# Z_line_07.net
KiCad netlist of a schematic drawn in Altium Designer
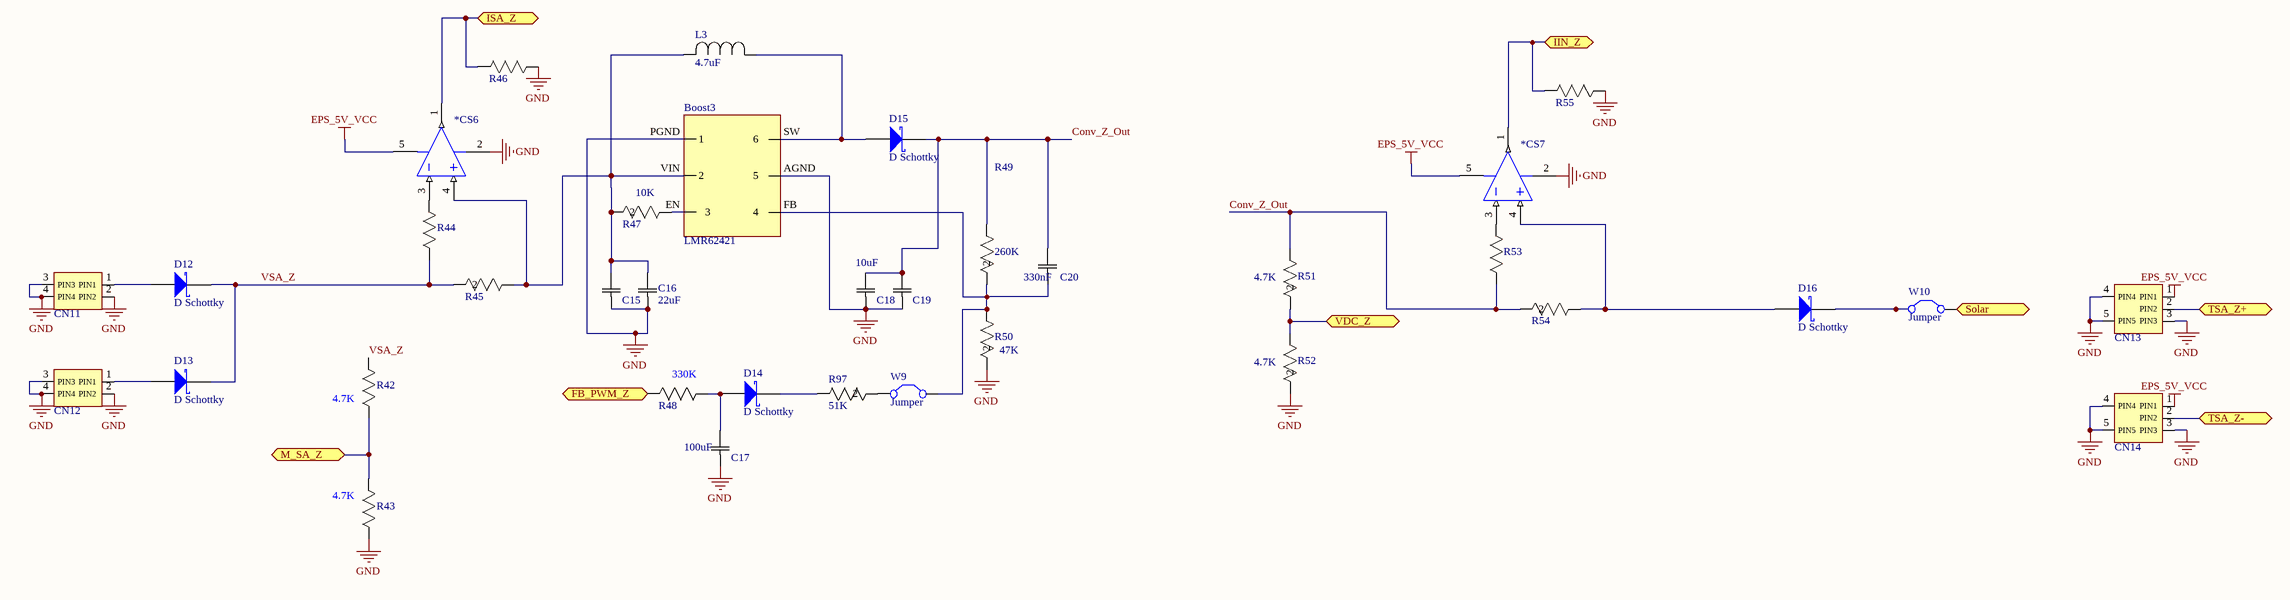
[diagram p0: Z_line_07.SchDoc]

(export (version "E")
  (design (tool "Eeschema 10.0.6"))
  (components
    (comp (ref "*CS6")
      (value "CS6")
      (footprint "LT-S5-5-TSOT-23_N")
      (fields
        (field (name "LINEAR TECHNOLOGY PART NUMBER") "LT6106")
        (field (name "MANUFACTURER") "Linear Technology")
        (field (name "PARTNUMBER") "LT6106HS5#TRMPBF")
      )
      (libsource (lib "Linear Technology Operational Amplifiers (LT2000-LT6000)") (part "LT6106HS5#TRMPBF"))
    )
    (comp (ref "*CS7")
      (value "CS7")
      (footprint "LT-S5-5-TSOT-23_N")
      (fields
        (field (name "LINEAR TECHNOLOGY PART NUMBER") "LT6106")
        (field (name "MANUFACTURER") "Linear Technology")
        (field (name "PARTNUMBER") "LT6106HS5#TRMPBF")
      )
      (libsource (lib "Linear Technology Operational Amplifiers (LT2000-LT6000)") (part "LT6106HS5#TRMPBF"))
    )
    (comp (ref "Boost3")
      (value "LMR62421")
      (footprint "PcbLib_2:LMR62421")
      (description "LMR62421XSDDEMO: 12V @ 500mA, 2.7 ~ 5.5V in")
      (libsource (lib "LMR62421_2") (part "Component_1"))
    )
    (comp (ref "C15")
      (value "GRM155R71H103KA8")
      (footprint "RC0805N")
      (description "Ceramic Capacitor 0402")
      (fields
        (field (name "MANUFACTURER_PART_NUMBER") "GRM155R71H103KA88D")
        (field (name "COPYRIGHT") "Copyright (C) 2015 Accelerated Designs. All rights reserved")
      )
      (libsource (lib "Schlib1") (part "GRM155R71H103KA8"))
    )
    (comp (ref "C16")
      (value "22uF")
      (footprint "RC0805N")
      (description "Ceramic Capacitor")
      (fields
        (field (name "MANUFACTURER_PART_NUMBER") "GRM155R71H103KA88D")
        (field (name "COPYRIGHT") "Copyright (C) 2015 Accelerated Designs. All rights reserved")
      )
      (libsource (lib "PCDU_Library") (part "GRM155R71H103KA8"))
    )
    (comp (ref "C17")
      (value "100uF")
      (footprint "RC0805N")
      (description "Ceramic Capacitor 47uF 0603")
      (fields
        (field (name "MANUFACTURER_PART_NUMBER") "GRM188R71H472KA01D")
        (field (name "COPYRIGHT") "Copyright (C) 2015 Accelerated Designs. All rights reserved")
      )
      (libsource (lib "Schlib1") (part "GRM188R71H472KA0"))
    )
    (comp (ref "C18")
      (value "10uF")
      (footprint "PcbLib1:RC0805N")
      (description "Ceramic Capacitor 47uF 0603")
      (fields
        (field (name "MANUFACTURER_PART_NUMBER") "GRM188R71H472KA01D")
        (field (name "COPYRIGHT") "Copyright (C) 2015 Accelerated Designs. All rights reserved")
      )
      (libsource (lib "PCDU_Library") (part "GRM188R71H472KA0"))
    )
    (comp (ref "C19")
      (value "GRM155R71H103KA8")
      (footprint "RC0805N")
      (description "Ceramic Capacitor 0402")
      (fields
        (field (name "MANUFACTURER_PART_NUMBER") "GRM155R71H103KA88D")
        (field (name "COPYRIGHT") "Copyright (C) 2015 Accelerated Designs. All rights reserved")
      )
      (libsource (lib "Schlib1") (part "GRM155R71H103KA8"))
    )
    (comp (ref "C20")
      (value "330nF")
      (footprint "RC0805N")
      (description "Ceramic Capacitor")
      (fields
        (field (name "MANUFACTURER_PART_NUMBER") "GRM155R71H103KA88D")
        (field (name "COPYRIGHT") "Copyright (C) 2015 Accelerated Designs. All rights reserved")
      )
      (libsource (lib "PCDU_Library") (part "GRM155R71H103KA8"))
    )
    (comp (ref "CN11")
      (value "SM02B-SRSS")
      (footprint "2pins")
      (description "CONN HEADER SH 2POS SIDE 1MM TIN")
      (fields
        (field (name "DIGI-KEY PART NUMBER") "455-1802-1-ND")
        (field (name "MANUFACTURER PART NUMBER") "SM02B-SRSS-TB(LF)(SN)")
      )
      (libsource (lib "EPS_lib") (part "2Pin_Connector"))
    )
    (comp (ref "CN12")
      (value "SM02B-SRSS")
      (footprint "2pins")
      (description "CONN HEADER SH 2POS SIDE 1MM TIN")
      (fields
        (field (name "DIGI-KEY PART NUMBER") "455-1802-1-ND")
        (field (name "MANUFACTURER PART NUMBER") "SM02B-SRSS-TB(LF)(SN)")
      )
      (libsource (lib "EPS_lib") (part "2Pin_Connector"))
    )
    (comp (ref "CN13")
      (value "SM03B-SRSS")
      (footprint "PcbLib1:3pins")
      (description "CONN HEADER SH 3POS SIDE 1MM TIN")
      (fields
        (field (name "DIGI-KEY PART NUMBER") "455-1803-1-ND")
        (field (name "MANUFACTURER PART NUMBER") "SM03B-SRSS-TB(LF)(SN)")
      )
      (libsource (lib "EPS_lib") (part "3PIN_Connector"))
    )
    (comp (ref "CN14")
      (value "SM03B-SRSS")
      (footprint "PcbLib1:3pins")
      (description "CONN HEADER SH 3POS SIDE 1MM TIN")
      (fields
        (field (name "DIGI-KEY PART NUMBER") "455-1803-1-ND")
        (field (name "MANUFACTURER PART NUMBER") "SM03B-SRSS-TB(LF)(SN)")
      )
      (libsource (lib "EPS_lib") (part "3PIN_Connector"))
    )
    (comp (ref "D12")
      (value "D Schottky")
      (footprint "SMB")
      (description "Schottky Diode, 1A")
      (fields (field (name "PUBLISHER") "Altium Limited"))
      (libsource (lib "PCDU_Library") (part "D Schottky"))
    )
    (comp (ref "D13")
      (value "D Schottky")
      (footprint "SMB")
      (description "Schottky Diode, 1A")
      (fields (field (name "PUBLISHER") "Altium Limited"))
      (libsource (lib "PCDU_Library") (part "D Schottky"))
    )
    (comp (ref "D14")
      (value "D Schottky")
      (footprint "SMB")
      (description "Schottky Diode, 1A")
      (fields (field (name "PUBLISHER") "Altium Limited"))
      (libsource (lib "Schlib1") (part "D Schottky"))
    )
    (comp (ref "D15")
      (value "D Schottky")
      (footprint "SMB")
      (description "Schottky Diode, 1A")
      (fields (field (name "PUBLISHER") "Altium Limited"))
      (libsource (lib "PCDU_Library") (part "D Schottky"))
    )
    (comp (ref "D16")
      (value "D Schottky")
      (footprint "SMB")
      (description "Schottky Diode, 1A")
      (fields (field (name "PUBLISHER") "Altium Limited"))
      (libsource (lib "PCDU_Library") (part "D Schottky"))
    )
    (comp (ref "L3")
      (value "4.7uF")
      (footprint "IND_SPM6530")
      (description "Inductor, 4.7uH")
      (fields
        (field (name "MANUFACTURER_PART_NUMBER") "SPM6530T-4R7M")
        (field (name "COPYRIGHT") "Copyright (C) 2015 Accelerated Designs. All rights reserved")
      )
      (libsource (lib "PCDU_Library") (part "SPM6530T-4R7M"))
    )
    (comp (ref "R42")
      (value "RC0805FR")
      (footprint "RC0805N")
      (description "Thick Film Resistors 0805")
      (fields
        (field (name "DIGIKEYPARTNUMBER") "311-4.70KCRTR-ND")
        (field (name "MANUFACTURER_PART_NUMBER") "RC0805FR-074K7L")
        (field (name "RESISTANCE_(OHMS)") "4.7K")
        (field (name "COPYRIGHT") "Copyright (C) 2015 Accelerated Designs. All rights reserved")
      )
      (libsource (lib "Schlib1") (part "RC0805FR"))
    )
    (comp (ref "R43")
      (value "RC0805FR")
      (footprint "RC0805N")
      (description "Thick Film Resistors 0805")
      (fields
        (field (name "DIGIKEYPARTNUMBER") "311-4.70KCRTR-ND")
        (field (name "MANUFACTURER_PART_NUMBER") "RC0805FR-074K7L")
        (field (name "RESISTANCE_(OHMS)") "4.7K")
        (field (name "COPYRIGHT") "Copyright (C) 2015 Accelerated Designs. All rights reserved")
      )
      (libsource (lib "Schlib1") (part "RC0805FR"))
    )
    (comp (ref "R44")
      (value "RC0805FR")
      (footprint "RC0805N")
      (description "Thick Film Resistors 0805")
      (fields
        (field (name "DIGIKEYPARTNUMBER") "311-4.70KCRTR-ND")
        (field (name "MANUFACTURER_PART_NUMBER") "RC0805FR-074K7L")
        (field (name "COPYRIGHT") "Copyright (C) 2015 Accelerated Designs. All rights reserved")
      )
      (libsource (lib "Schlib1") (part "RC0805FR"))
    )
    (comp (ref "R45")
      (value "RL0805FR-070R1L")
      (footprint "RC0805N")
      (description "Sense Resistor 100m ohm 0805")
      (fields
        (field (name "DIGIKEYPARTNUMBER") "311-.10STR-ND")
        (field (name "TOLERANCE") "Â±1%")
        (field (name "COPYRIGHT") "Copyright (C) 2015 Accelerated Designs. All rights reserved")
      )
      (libsource (lib "Schlib1") (part "RL0805FR-070R1L"))
    )
    (comp (ref "R46")
      (value "RC0805FR")
      (footprint "RC0805N")
      (description "Thick Film Resistors 0805")
      (fields
        (field (name "DIGIKEYPARTNUMBER") "311-4.70KCRTR-ND")
        (field (name "MANUFACTURER_PART_NUMBER") "RC0805FR-074K7L")
        (field (name "COPYRIGHT") "Copyright (C) 2015 Accelerated Designs. All rights reserved")
      )
      (libsource (lib "Schlib1") (part "RC0805FR"))
    )
    (comp (ref "R47")
      (value "10K")
      (footprint "RC0805N")
      (description "Thick Film Resistors 0805")
      (fields
        (field (name "DIGIKEYPARTNUMBER") "311-4.70KCRTR-ND")
        (field (name "MANUFACTURER_PART_NUMBER") "RC0805FR-074K7L")
        (field (name "COPYRIGHT") "Copyright (C) 2015 Accelerated Designs. All rights reserved")
      )
      (libsource (lib "PCDU_Library") (part "RC0805FR"))
    )
    (comp (ref "R48")
      (value "RC0805FR")
      (footprint "RC0805N")
      (description "Thick Film Resistors 0805")
      (fields
        (field (name "DIGIKEYPARTNUMBER") "311-4.70KCRTR-ND")
        (field (name "MANUFACTURER_PART_NUMBER") "RC0805FR-074K7L")
        (field (name "RESISTANCE_(OHMS)") "330K")
        (field (name "COPYRIGHT") "Copyright (C) 2015 Accelerated Designs. All rights reserved")
      )
      (libsource (lib "Schlib1") (part "RC0805FR"))
    )
    (comp (ref "R49")
      (value "260K")
      (footprint "RC0805N")
      (description "Thick Film Resistors 0805")
      (fields
        (field (name "DIGIKEYPARTNUMBER") "311-4.70KCRTR-ND")
        (field (name "MANUFACTURER_PART_NUMBER") "RC0805FR-074K7L")
        (field (name "COPYRIGHT") "Copyright (C) 2015 Accelerated Designs. All rights reserved")
      )
      (libsource (lib "PCDU_Library") (part "RC0805FR"))
    )
    (comp (ref "R50")
      (value "47K")
      (footprint "RC0805N")
      (description "Thick Film Resistors 0805")
      (fields
        (field (name "DIGIKEYPARTNUMBER") "311-4.70KCRTR-ND")
        (field (name "MANUFACTURER_PART_NUMBER") "RC0805FR-074K7L")
        (field (name "COPYRIGHT") "Copyright (C) 2015 Accelerated Designs. All rights reserved")
      )
      (libsource (lib "PCDU_Library") (part "RC0805FR"))
    )
    (comp (ref "R51")
      (value "4.7K")
      (footprint "RC0805N")
      (description "Thick Film Resistors 0805")
      (fields
        (field (name "DIGIKEYPARTNUMBER") "311-4.70KCRTR-ND")
        (field (name "MANUFACTURER_PART_NUMBER") "RC0805FR-074K7L")
        (field (name "COPYRIGHT") "Copyright (C) 2015 Accelerated Designs. All rights reserved")
      )
      (libsource (lib "PCDU_Library") (part "RC0805FR"))
    )
    (comp (ref "R52")
      (value "4.7K")
      (footprint "RC0805N")
      (description "Thick Film Resistors 0805")
      (fields
        (field (name "DIGIKEYPARTNUMBER") "311-4.70KCRTR-ND")
        (field (name "MANUFACTURER_PART_NUMBER") "RC0805FR-074K7L")
        (field (name "COPYRIGHT") "Copyright (C) 2015 Accelerated Designs. All rights reserved")
      )
      (libsource (lib "PCDU_Library") (part "RC0805FR"))
    )
    (comp (ref "R53")
      (value "RC0805FR")
      (footprint "RC0805N")
      (description "Thick Film Resistors 0805")
      (fields
        (field (name "DIGIKEYPARTNUMBER") "311-4.70KCRTR-ND")
        (field (name "MANUFACTURER_PART_NUMBER") "RC0805FR-074K7L")
        (field (name "COPYRIGHT") "Copyright (C) 2015 Accelerated Designs. All rights reserved")
      )
      (libsource (lib "Schlib1") (part "RC0805FR"))
    )
    (comp (ref "R54")
      (value "RL0805FR-070R1L")
      (footprint "RC0805N")
      (description "Sense Resistor 100m ohm 0805")
      (fields
        (field (name "DIGIKEYPARTNUMBER") "311-.10STR-ND")
        (field (name "TOLERANCE") "Â±1%")
        (field (name "COPYRIGHT") "Copyright (C) 2015 Accelerated Designs. All rights reserved")
      )
      (libsource (lib "Schlib1") (part "RL0805FR-070R1L"))
    )
    (comp (ref "R55")
      (value "RC0805FR")
      (footprint "RC0805N")
      (description "Thick Film Resistors 0805")
      (fields
        (field (name "DIGIKEYPARTNUMBER") "311-4.70KCRTR-ND")
        (field (name "MANUFACTURER_PART_NUMBER") "RC0805FR-074K7L")
        (field (name "COPYRIGHT") "Copyright (C) 2015 Accelerated Designs. All rights reserved")
      )
      (libsource (lib "Schlib1") (part "RC0805FR"))
    )
    (comp (ref "R97")
      (value "51K")
      (footprint "RC0805N")
      (description "Thick Film Resistors 0805")
      (fields
        (field (name "DIGIKEYPARTNUMBER") "311-4.70KCRTR-ND")
        (field (name "MANUFACTURER_PART_NUMBER") "RC0805FR-074K7L")
        (field (name "COPYRIGHT") "Copyright (C) 2015 Accelerated Designs. All rights reserved")
      )
      (libsource (lib "PCDU_Library") (part "RC0805FR"))
    )
    (comp (ref "W9")
      (value "Jumper")
      (footprint "PcbLib1:RAD-0.1")
      (description "Jumper Wire")
      (fields (field (name "PUBLISHER") "Altium Limited"))
      (libsource (lib "PCDU_Library") (part "Jumper"))
    )
    (comp (ref "W10")
      (value "Jumper")
      (footprint "PcbLib1:RAD-0.1")
      (description "Jumper Wire")
      (fields (field (name "PUBLISHER") "Altium Limited"))
      (libsource (lib "PCDU_Library") (part "Jumper"))
    )
  )
  (nets
    (net (code "1") (name "/Conv_Z_Out") (class "Default")
      (node (ref "C18") (pin "2") (pinfunction "2_2") (pintype "passive"))
      (node (ref "C19") (pin "2") (pinfunction "2_2") (pintype "passive"))
      (node (ref "C20") (pin "2") (pinfunction "2_2") (pintype "passive"))
      (node (ref "D15") (pin "2") (pinfunction "K_2") (pintype "passive"))
      (node (ref "R49") (pin "1") (pinfunction "1_1") (pintype "passive"))
      (node (ref "R51") (pin "1") (pinfunction "1_1") (pintype "passive"))
      (node (ref "R53") (pin "2") (pinfunction "2_2") (pintype "passive"))
      (node (ref "R54") (pin "2") (pinfunction "2_2") (pintype "passive"))
    )
    (net (code "2") (name "/FB_PWM_Z") (class "Default")
      (node (ref "R48") (pin "2") (pinfunction "2_2") (pintype "passive"))
    )
    (net (code "3") (name "/IIN_Z") (class "Default")
      (node (ref "*CS7") (pin "1") (pinfunction "OUT_1") (pintype "output"))
      (node (ref "R55") (pin "1") (pinfunction "1_1") (pintype "passive"))
    )
    (net (code "4") (name "/ISA_Z") (class "Default")
      (node (ref "*CS6") (pin "1") (pinfunction "OUT_1") (pintype "output"))
      (node (ref "R46") (pin "1") (pinfunction "1_1") (pintype "passive"))
    )
    (net (code "5") (name "/M_SA_Z") (class "Default")
      (node (ref "R42") (pin "2") (pinfunction "2_2") (pintype "passive"))
      (node (ref "R43") (pin "1") (pinfunction "1_1") (pintype "passive"))
    )
    (net (code "6") (name "/Solar") (class "Default")
      (node (ref "W10") (pin "2") (pinfunction "C2_2") (pintype "passive"))
    )
    (net (code "7") (name "/TSA_Z+") (class "Default")
      (node (ref "CN13") (pin "2") (pinfunction "PIN2_2") (pintype "passive"))
    )
    (net (code "8") (name "/TSA_Z-") (class "Default")
      (node (ref "CN14") (pin "2") (pinfunction "PIN2_2") (pintype "passive"))
    )
    (net (code "9") (name "/VDC_Z") (class "Default")
      (node (ref "R51") (pin "2") (pinfunction "2_2") (pintype "passive"))
      (node (ref "R52") (pin "1") (pinfunction "1_1") (pintype "passive"))
    )
    (net (code "10") (name "/VSA_Z") (class "Default")
      (node (ref "D12") (pin "2") (pinfunction "K_2") (pintype "passive"))
      (node (ref "D13") (pin "2") (pinfunction "K_2") (pintype "passive"))
      (node (ref "R42") (pin "1") (pinfunction "1_1") (pintype "passive"))
      (node (ref "R44") (pin "2") (pinfunction "2_2") (pintype "passive"))
      (node (ref "R45") (pin "2") (pinfunction "2_2") (pintype "passive"))
    )
    (net (code "11") (name "EPS_5V_VCC") (class "Default")
      (node (ref "*CS6") (pin "5") (pinfunction "V+_5") (pintype "power_in"))
      (node (ref "*CS7") (pin "5") (pinfunction "V+_5") (pintype "power_in"))
      (node (ref "CN13") (pin "1") (pinfunction "PIN1_1") (pintype "passive"))
      (node (ref "CN14") (pin "1") (pinfunction "PIN1_1") (pintype "passive"))
    )
    (net (code "12") (name "GND") (class "Default")
      (node (ref "*CS6") (pin "2") (pinfunction "V-_2") (pintype "power_in"))
      (node (ref "*CS7") (pin "2") (pinfunction "V-_2") (pintype "power_in"))
      (node (ref "Boost3") (pin "AGND") (pinfunction "5_AGND") (pintype "passive"))
      (node (ref "Boost3") (pin "PGND") (pinfunction "1_PGND") (pintype "passive"))
      (node (ref "C15") (pin "1") (pinfunction "1_1") (pintype "passive"))
      (node (ref "C16") (pin "1") (pinfunction "1_1") (pintype "passive"))
      (node (ref "C17") (pin "1") (pinfunction "1_1") (pintype "passive"))
      (node (ref "C18") (pin "1") (pinfunction "1_1") (pintype "passive"))
      (node (ref "C19") (pin "1") (pinfunction "1_1") (pintype "passive"))
      (node (ref "CN11") (pin "2") (pinfunction "PIN2_2") (pintype "passive"))
      (node (ref "CN11") (pin "3") (pinfunction "PIN3_3") (pintype "passive"))
      (node (ref "CN11") (pin "4") (pinfunction "PIN4_4") (pintype "passive"))
      (node (ref "CN12") (pin "2") (pinfunction "PIN2_2") (pintype "passive"))
      (node (ref "CN12") (pin "3") (pinfunction "PIN3_3") (pintype "passive"))
      (node (ref "CN12") (pin "4") (pinfunction "PIN4_4") (pintype "passive"))
      (node (ref "CN13") (pin "3") (pinfunction "PIN3_3") (pintype "passive"))
      (node (ref "CN13") (pin "4") (pinfunction "PIN4_4") (pintype "passive"))
      (node (ref "CN13") (pin "5") (pinfunction "PIN5_5") (pintype "passive"))
      (node (ref "CN14") (pin "3") (pinfunction "PIN3_3") (pintype "passive"))
      (node (ref "CN14") (pin "4") (pinfunction "PIN4_4") (pintype "passive"))
      (node (ref "CN14") (pin "5") (pinfunction "PIN5_5") (pintype "passive"))
      (node (ref "R43") (pin "2") (pinfunction "2_2") (pintype "passive"))
      (node (ref "R46") (pin "2") (pinfunction "2_2") (pintype "passive"))
      (node (ref "R50") (pin "2") (pinfunction "2_2") (pintype "passive"))
      (node (ref "R52") (pin "2") (pinfunction "2_2") (pintype "passive"))
      (node (ref "R55") (pin "2") (pinfunction "2_2") (pintype "passive"))
    )
    (net (code "13") (name "Net-(*CS6-+IN)") (class "Default")
      (node (ref "*CS6") (pin "4") (pinfunction "+IN_4") (pintype "input"))
      (node (ref "Boost3") (pin "VIN") (pinfunction "2_VIN") (pintype "passive"))
      (node (ref "C15") (pin "2") (pinfunction "2_2") (pintype "passive"))
      (node (ref "C16") (pin "2") (pinfunction "2_2") (pintype "passive"))
      (node (ref "L3") (pin "2") (pinfunction "2_2") (pintype "passive"))
      (node (ref "R45") (pin "1") (pinfunction "1_1") (pintype "passive"))
      (node (ref "R47") (pin "2") (pinfunction "2_2") (pintype "passive"))
    )
    (net (code "14") (name "Net-(*CS6--IN)") (class "Default")
      (node (ref "*CS6") (pin "3") (pinfunction "-IN_3") (pintype "input"))
      (node (ref "R44") (pin "1") (pinfunction "1_1") (pintype "passive"))
    )
    (net (code "15") (name "Net-(*CS7-+IN)") (class "Default")
      (node (ref "*CS7") (pin "4") (pinfunction "+IN_4") (pintype "input"))
      (node (ref "D16") (pin "1") (pinfunction "A_1") (pintype "passive"))
      (node (ref "R54") (pin "1") (pinfunction "1_1") (pintype "passive"))
    )
    (net (code "16") (name "Net-(*CS7--IN)") (class "Default")
      (node (ref "*CS7") (pin "3") (pinfunction "-IN_3") (pintype "input"))
      (node (ref "R53") (pin "1") (pinfunction "1_1") (pintype "passive"))
    )
    (net (code "17") (name "Net-(Boost3-3)") (class "Default")
      (node (ref "Boost3") (pin "EN") (pinfunction "3_EN") (pintype "passive"))
      (node (ref "R47") (pin "1") (pinfunction "1_1") (pintype "passive"))
    )
    (net (code "18") (name "Net-(Boost3-4)") (class "Default")
      (node (ref "Boost3") (pin "FB") (pinfunction "4_FB") (pintype "passive"))
      (node (ref "C20") (pin "1") (pinfunction "1_1") (pintype "passive"))
      (node (ref "R49") (pin "2") (pinfunction "2_2") (pintype "passive"))
      (node (ref "R50") (pin "1") (pinfunction "1_1") (pintype "passive"))
      (node (ref "W9") (pin "2") (pinfunction "C2_2") (pintype "passive"))
    )
    (net (code "19") (name "Net-(Boost3-6)") (class "Default")
      (node (ref "Boost3") (pin "SW") (pinfunction "6_SW") (pintype "passive"))
      (node (ref "D15") (pin "1") (pinfunction "A_1") (pintype "passive"))
      (node (ref "L3") (pin "1") (pinfunction "1_1") (pintype "passive"))
    )
    (net (code "20") (name "Net-(CN11-PIN1)") (class "Default")
      (node (ref "CN11") (pin "1") (pinfunction "PIN1_1") (pintype "passive"))
      (node (ref "D12") (pin "1") (pinfunction "A_1") (pintype "passive"))
    )
    (net (code "21") (name "Net-(CN12-PIN1)") (class "Default")
      (node (ref "CN12") (pin "1") (pinfunction "PIN1_1") (pintype "passive"))
      (node (ref "D13") (pin "1") (pinfunction "A_1") (pintype "passive"))
    )
    (net (code "22") (name "Net-(D14-A)") (class "Default")
      (node (ref "C17") (pin "2") (pinfunction "2_2") (pintype "passive"))
      (node (ref "D14") (pin "1") (pinfunction "A_1") (pintype "passive"))
      (node (ref "R48") (pin "1") (pinfunction "1_1") (pintype "passive"))
    )
    (net (code "23") (name "Net-(D14-K)") (class "Default")
      (node (ref "D14") (pin "2") (pinfunction "K_2") (pintype "passive"))
      (node (ref "R97") (pin "1") (pinfunction "1_1") (pintype "passive"))
    )
    (net (code "24") (name "Net-(D16-K)") (class "Default")
      (node (ref "D16") (pin "2") (pinfunction "K_2") (pintype "passive"))
      (node (ref "W10") (pin "1") (pinfunction "C1_1") (pintype "passive"))
    )
    (net (code "25") (name "Net-(W9-C1)") (class "Default")
      (node (ref "R97") (pin "2") (pinfunction "2_2") (pintype "passive"))
      (node (ref "W9") (pin "1") (pinfunction "C1_1") (pintype "passive"))
    )
  )
)
